# Motorsteuerung_op.net
KiCad netlist of a schematic drawn in EAGLE
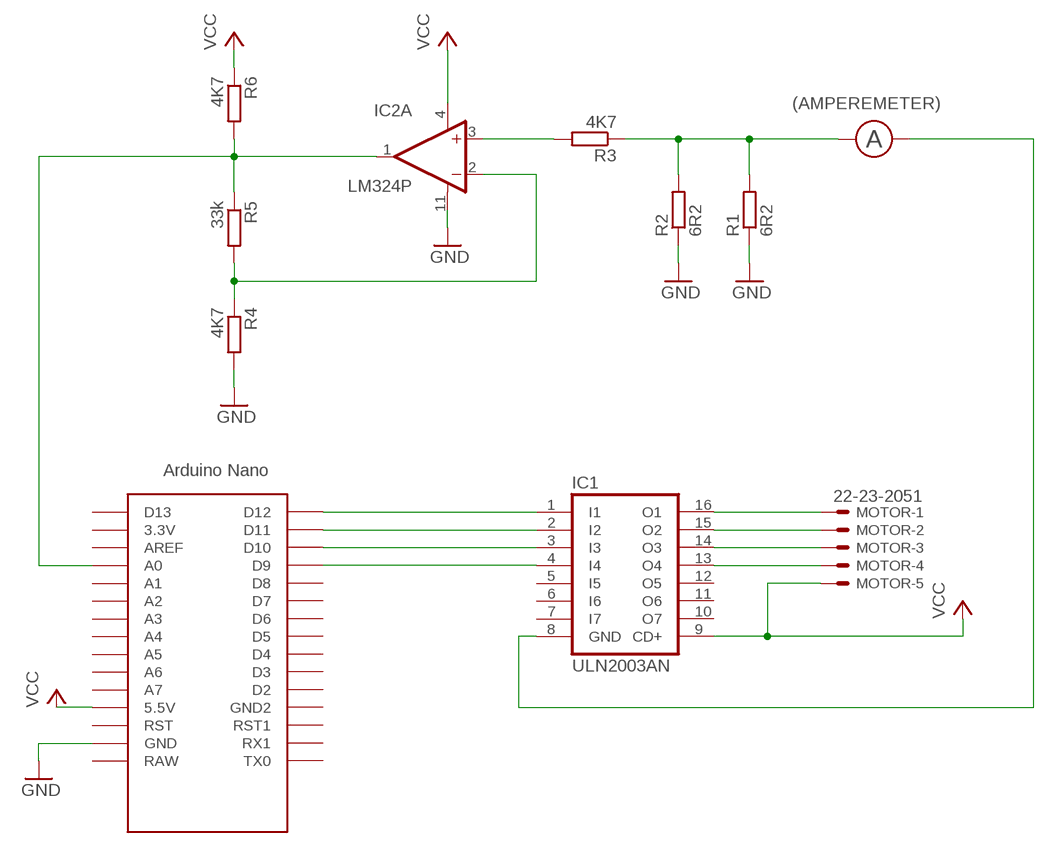
[diagram p0: schematic, sheet 1]

(export (version "E")
  (design (tool "Eeschema 10.0.6"))
  (components
    (comp (ref "IC1")
      (value "ULN2003AN")
      (footprint "eagle-import:DIL16")
      (libsource (lib "eagle-import") (part "ULN2003AN"))
    )
    (comp (ref "IC2")
      (value "LM324P")
      (footprint "eagle-import:DIL14")
      (libsource (lib "eagle-import") (part "LM324P"))
    )
    (comp (ref "MOTOR")
      (value "22-23-2051")
      (footprint "eagle-import:22-23-2051")
      (fields (field (name "MF") "MOLEX"))
      (libsource (lib "eagle-import") (part "22-23-2051"))
    )
    (comp (ref "R1")
      (value "6R2")
      (footprint "eagle-import:0207_10")
      (libsource (lib "eagle-import") (part "R-EU_0207/10"))
    )
    (comp (ref "R2")
      (value "6R2")
      (footprint "eagle-import:0207_10")
      (libsource (lib "eagle-import") (part "R-EU_0207/10"))
    )
    (comp (ref "R3")
      (value "4K7")
      (footprint "eagle-import:0207_10")
      (libsource (lib "eagle-import") (part "R-EU_0207/10"))
    )
    (comp (ref "R4")
      (value "4K7")
      (footprint "eagle-import:0207_10")
      (libsource (lib "eagle-import") (part "R-EU_0207/10"))
    )
    (comp (ref "R5")
      (value "33k")
      (footprint "eagle-import:0207_10")
      (libsource (lib "eagle-import") (part "R-EU_0207/10"))
    )
    (comp (ref "R6")
      (value "4K7")
      (footprint "eagle-import:0207_10")
      (libsource (lib "eagle-import") (part "R-EU_0207/10"))
    )
    (comp (ref "U$1")
      (value "NANO")
      (footprint "eagle-import:NANO")
      (libsource (lib "eagle-import") (part "NANO"))
    )
  )
  (nets
    (net (code "1") (name "GND") (class "Default")
      (node (ref "IC2") (pin "11") (pinfunction "V-_11") (pintype "power_in"))
      (node (ref "R1") (pin "1") (pinfunction "1_1") (pintype "passive"))
      (node (ref "R2") (pin "1") (pinfunction "1_1") (pintype "passive"))
      (node (ref "R4") (pin "2") (pinfunction "2_2") (pintype "passive"))
      (node (ref "U$1") (pin "GND") (pinfunction "GND_GND") (pintype "bidirectional"))
    )
    (net (code "2") (name "Net-(IC1-GND)") (class "Default")
      (node (ref "IC1") (pin "8") (pinfunction "GND_8") (pintype "power_in"))
    )
    (net (code "3") (name "Net-(IC1-I1)") (class "Default")
      (node (ref "IC1") (pin "1") (pinfunction "I1_1") (pintype "input"))
      (node (ref "U$1") (pin "D12") (pinfunction "D12_D12") (pintype "bidirectional"))
    )
    (net (code "4") (name "Net-(IC1-I2)") (class "Default")
      (node (ref "IC1") (pin "2") (pinfunction "I2_2") (pintype "input"))
      (node (ref "U$1") (pin "D11") (pinfunction "D11_D11") (pintype "bidirectional"))
    )
    (net (code "5") (name "Net-(IC1-I3)") (class "Default")
      (node (ref "IC1") (pin "3") (pinfunction "I3_3") (pintype "input"))
      (node (ref "U$1") (pin "D10") (pinfunction "D10_D10") (pintype "bidirectional"))
    )
    (net (code "6") (name "Net-(IC1-I4)") (class "Default")
      (node (ref "IC1") (pin "4") (pinfunction "I4_4") (pintype "input"))
      (node (ref "U$1") (pin "D9") (pinfunction "D9_D9") (pintype "bidirectional"))
    )
    (net (code "7") (name "Net-(IC1-O1)") (class "Default")
      (node (ref "IC1") (pin "16") (pinfunction "O1_16") (pintype "open_collector"))
      (node (ref "MOTOR") (pin "1") (pinfunction "S_1") (pintype "passive"))
    )
    (net (code "8") (name "Net-(IC1-O2)") (class "Default")
      (node (ref "IC1") (pin "15") (pinfunction "O2_15") (pintype "open_collector"))
      (node (ref "MOTOR") (pin "2") (pinfunction "S_2") (pintype "passive"))
    )
    (net (code "9") (name "Net-(IC1-O3)") (class "Default")
      (node (ref "IC1") (pin "14") (pinfunction "O3_14") (pintype "open_collector"))
      (node (ref "MOTOR") (pin "3") (pinfunction "S_3") (pintype "passive"))
    )
    (net (code "10") (name "Net-(IC1-O4)") (class "Default")
      (node (ref "IC1") (pin "13") (pinfunction "O4_13") (pintype "open_collector"))
      (node (ref "MOTOR") (pin "4") (pinfunction "S_4") (pintype "passive"))
    )
    (net (code "11") (name "Net-(IC2A-+IN)") (class "Default")
      (node (ref "IC2") (pin "3") (pinfunction "+IN_3") (pintype "input"))
      (node (ref "R3") (pin "2") (pinfunction "2_2") (pintype "passive"))
    )
    (net (code "12") (name "Net-(IC2A--IN)") (class "Default")
      (node (ref "IC2") (pin "2") (pinfunction "-IN_2") (pintype "input"))
      (node (ref "R4") (pin "1") (pinfunction "1_1") (pintype "passive"))
      (node (ref "R5") (pin "2") (pinfunction "2_2") (pintype "passive"))
    )
    (net (code "13") (name "Net-(IC2A-OUT)") (class "Default")
      (node (ref "IC2") (pin "1") (pinfunction "OUT_1") (pintype "output"))
      (node (ref "R5") (pin "1") (pinfunction "1_1") (pintype "passive"))
      (node (ref "R6") (pin "2") (pinfunction "2_2") (pintype "passive"))
      (node (ref "U$1") (pin "A0") (pinfunction "A0_A0") (pintype "bidirectional"))
    )
    (net (code "14") (name "Net-(R1-Pad2)") (class "Default")
      (node (ref "R1") (pin "2") (pinfunction "2_2") (pintype "passive"))
      (node (ref "R2") (pin "2") (pinfunction "2_2") (pintype "passive"))
      (node (ref "R3") (pin "1") (pinfunction "1_1") (pintype "passive"))
    )
    (net (code "15") (name "VCC") (class "Default")
      (node (ref "IC1") (pin "9") (pinfunction "CD+_9") (pintype "passive"))
      (node (ref "IC2") (pin "4") (pinfunction "V+_4") (pintype "power_in"))
      (node (ref "MOTOR") (pin "5") (pinfunction "S_5") (pintype "passive"))
      (node (ref "R6") (pin "1") (pinfunction "1_1") (pintype "passive"))
      (node (ref "U$1") (pin "5V") (pinfunction "5.5V_5V") (pintype "bidirectional"))
    )
    (net (code "16") (name "unconnected-(IC1-I5-Pad5)") (class "Default")
      (node (ref "IC1") (pin "5") (pinfunction "I5_5") (pintype "input"))
    )
    (net (code "17") (name "unconnected-(IC1-I6-Pad6)") (class "Default")
      (node (ref "IC1") (pin "6") (pinfunction "I6_6") (pintype "input"))
    )
    (net (code "18") (name "unconnected-(IC1-I7-Pad7)") (class "Default")
      (node (ref "IC1") (pin "7") (pinfunction "I7_7") (pintype "input"))
    )
    (net (code "19") (name "unconnected-(IC1-O5-Pad12)") (class "Default")
      (node (ref "IC1") (pin "12") (pinfunction "O5_12") (pintype "open_collector"))
    )
    (net (code "20") (name "unconnected-(IC1-O6-Pad11)") (class "Default")
      (node (ref "IC1") (pin "11") (pinfunction "O6_11") (pintype "open_collector"))
    )
    (net (code "21") (name "unconnected-(IC1-O7-Pad10)") (class "Default")
      (node (ref "IC1") (pin "10") (pinfunction "O7_10") (pintype "open_collector"))
    )
    (net (code "22") (name "unconnected-(U$1-GND2-PadGND1)") (class "Default")
      (node (ref "U$1") (pin "GND1") (pinfunction "GND2_GND1") (pintype "bidirectional"))
    )
    (net (code "23") (name "unconnected-(U$1-Pad3.3V)") (class "Default")
      (node (ref "U$1") (pin "3.3V") (pinfunction "3.3V_3.3V") (pintype "bidirectional"))
    )
    (net (code "24") (name "unconnected-(U$1-PadA1)") (class "Default")
      (node (ref "U$1") (pin "A1") (pinfunction "A1_A1") (pintype "bidirectional"))
    )
    (net (code "25") (name "unconnected-(U$1-PadA2)") (class "Default")
      (node (ref "U$1") (pin "A2") (pinfunction "A2_A2") (pintype "bidirectional"))
    )
    (net (code "26") (name "unconnected-(U$1-PadA3)") (class "Default")
      (node (ref "U$1") (pin "A3") (pinfunction "A3_A3") (pintype "bidirectional"))
    )
    (net (code "27") (name "unconnected-(U$1-PadA4)") (class "Default")
      (node (ref "U$1") (pin "A4") (pinfunction "A4_A4") (pintype "bidirectional"))
    )
    (net (code "28") (name "unconnected-(U$1-PadA5)") (class "Default")
      (node (ref "U$1") (pin "A5") (pinfunction "A5_A5") (pintype "bidirectional"))
    )
    (net (code "29") (name "unconnected-(U$1-PadA6)") (class "Default")
      (node (ref "U$1") (pin "A6") (pinfunction "A6_A6") (pintype "bidirectional"))
    )
    (net (code "30") (name "unconnected-(U$1-PadA7)") (class "Default")
      (node (ref "U$1") (pin "A7") (pinfunction "A7_A7") (pintype "bidirectional"))
    )
    (net (code "31") (name "unconnected-(U$1-PadAREF)") (class "Default")
      (node (ref "U$1") (pin "AREF") (pinfunction "AREF_AREF") (pintype "bidirectional"))
    )
    (net (code "32") (name "unconnected-(U$1-PadD2)") (class "Default")
      (node (ref "U$1") (pin "D2") (pinfunction "D2_D2") (pintype "bidirectional"))
    )
    (net (code "33") (name "unconnected-(U$1-PadD3)") (class "Default")
      (node (ref "U$1") (pin "D3") (pinfunction "D3_D3") (pintype "bidirectional"))
    )
    (net (code "34") (name "unconnected-(U$1-PadD4)") (class "Default")
      (node (ref "U$1") (pin "D4") (pinfunction "D4_D4") (pintype "bidirectional"))
    )
    (net (code "35") (name "unconnected-(U$1-PadD5)") (class "Default")
      (node (ref "U$1") (pin "D5") (pinfunction "D5_D5") (pintype "bidirectional"))
    )
    (net (code "36") (name "unconnected-(U$1-PadD6)") (class "Default")
      (node (ref "U$1") (pin "D6") (pinfunction "D6_D6") (pintype "bidirectional"))
    )
    (net (code "37") (name "unconnected-(U$1-PadD7)") (class "Default")
      (node (ref "U$1") (pin "D7") (pinfunction "D7_D7") (pintype "bidirectional"))
    )
    (net (code "38") (name "unconnected-(U$1-PadD8)") (class "Default")
      (node (ref "U$1") (pin "D8") (pinfunction "D8_D8") (pintype "bidirectional"))
    )
    (net (code "39") (name "unconnected-(U$1-PadD13)") (class "Default")
      (node (ref "U$1") (pin "D13") (pinfunction "D13_D13") (pintype "bidirectional"))
    )
    (net (code "40") (name "unconnected-(U$1-PadICSP1)") (class "Default")
      (node (ref "U$1") (pin "ICSP1") (pinfunction "ICSP1_ICSP1") (pintype "bidirectional"))
    )
    (net (code "41") (name "unconnected-(U$1-PadICSP2)") (class "Default")
      (node (ref "U$1") (pin "ICSP2") (pinfunction "ICSP2_ICSP2") (pintype "bidirectional"))
    )
    (net (code "42") (name "unconnected-(U$1-PadICSP3)") (class "Default")
      (node (ref "U$1") (pin "ICSP3") (pinfunction "ICSP3_ICSP3") (pintype "bidirectional"))
    )
    (net (code "43") (name "unconnected-(U$1-PadICSP4)") (class "Default")
      (node (ref "U$1") (pin "ICSP4") (pinfunction "ICSP4_ICSP4") (pintype "bidirectional"))
    )
    (net (code "44") (name "unconnected-(U$1-PadICSP5)") (class "Default")
      (node (ref "U$1") (pin "ICSP5") (pinfunction "ICSP5_ICSP5") (pintype "bidirectional"))
    )
    (net (code "45") (name "unconnected-(U$1-PadICSP6)") (class "Default")
      (node (ref "U$1") (pin "ICSP6") (pinfunction "ICSP6_ICSP6") (pintype "bidirectional"))
    )
    (net (code "46") (name "unconnected-(U$1-PadRAW)") (class "Default")
      (node (ref "U$1") (pin "RAW") (pinfunction "RAW_RAW") (pintype "bidirectional"))
    )
    (net (code "47") (name "unconnected-(U$1-PadRST)") (class "Default")
      (node (ref "U$1") (pin "RST") (pinfunction "RST_RST") (pintype "bidirectional"))
    )
    (net (code "48") (name "unconnected-(U$1-PadRST1)") (class "Default")
      (node (ref "U$1") (pin "RST1") (pinfunction "RST1_RST1") (pintype "bidirectional"))
    )
    (net (code "49") (name "unconnected-(U$1-PadRX1)") (class "Default")
      (node (ref "U$1") (pin "RX1") (pinfunction "RX1_RX1") (pintype "bidirectional"))
    )
    (net (code "50") (name "unconnected-(U$1-PadTX0)") (class "Default")
      (node (ref "U$1") (pin "TX0") (pinfunction "TX0_TX0") (pintype "bidirectional"))
    )
  )
)
